# 9__ID_Serial.net
KiCad netlist of a schematic drawn in Altium Designer
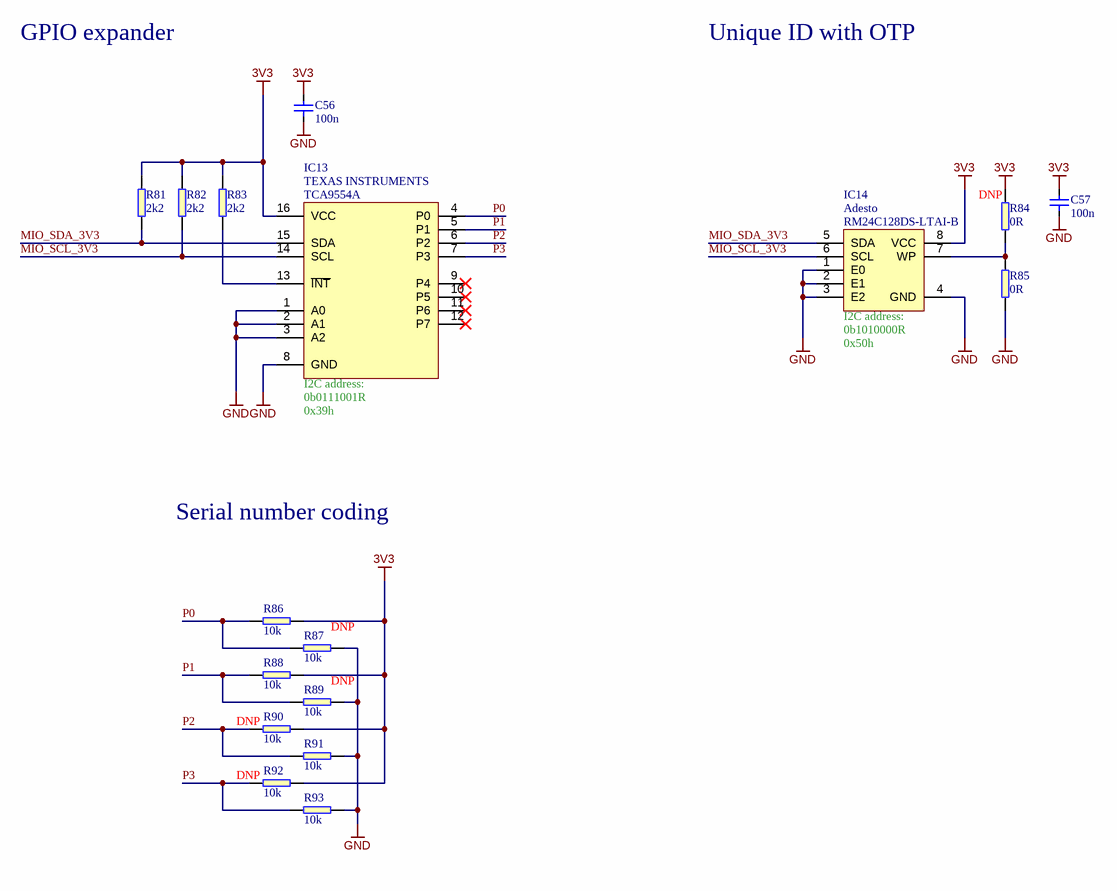
[diagram p0: [9]_ID_Serial.SchDoc]

(export (version "E")
  (design (tool "Eeschema 10.0.6"))
  (components
    (comp (ref "C56")
      (value "100n")
      (footprint "0402")
      (description "MLCC SMT Capacitor 100nF 0402")
      (fields (field (name "PART NUMBER") "C_100n_0402") (field (name "VOLTAGE") "10V"))
      (libsource (lib "Zynq-Video-Board-Rev-1.2") (part "C_100n_0402"))
    )
    (comp (ref "C57")
      (value "100n")
      (footprint "0402")
      (description "MLCC SMT Capacitor 100nF 0402")
      (fields (field (name "PART NUMBER") "C_100n_0402") (field (name "VOLTAGE") "10V"))
      (libsource (lib "Zynq-Video-Board-Rev-1.2") (part "C_100n_0402"))
    )
    (comp (ref "IC13")
      (value "TCA9554A")
      (footprint "DBQ0016A")
      (description "Remote 8bit I2C SMBus I/O expander")
      (fields (field (name "MANUFACTURER") "TEXAS INSTRUMENTS") (field (name "PART SYMBOL") "TCA9554A"))
      (libsource (lib "Zynq-Video-Board-Rev-1.2") (part "TCA9554A"))
    )
    (comp (ref "IC14")
      (value "RM24C128DS-LTAI-B")
      (footprint "TSSOP-8")
      (description "EEPROM with UID and OTP registers.")
      (fields
        (field (name "PART NUMBER") "RM24C128DS")
        (field (name "MANUFACTURER") "Adesto")
        (field (name "PART SYMBOL") "RM24C128DS-LTAI-B")
      )
      (libsource (lib "Zynq-Video-Board-Rev-1.2") (part "RM24C128DS"))
    )
    (comp (ref "R81")
      (value "2k2")
      (footprint "0402")
      (description "SMT Resistor 2k2 0402")
      (fields (field (name "PART NUMBER") "R_2k2_0402") (field (name "TOLERANCE") "5%"))
      (libsource (lib "Zynq-Video-Board-Rev-1.2") (part "R_2k2_0402"))
    )
    (comp (ref "R82")
      (value "2k2")
      (footprint "0402")
      (description "SMT Resistor 2k2 0402")
      (fields (field (name "PART NUMBER") "R_2k2_0402") (field (name "TOLERANCE") "5%"))
      (libsource (lib "Zynq-Video-Board-Rev-1.2") (part "R_2k2_0402"))
    )
    (comp (ref "R83")
      (value "2k2")
      (footprint "0402")
      (description "SMT Resistor 2k2 0402")
      (fields (field (name "PART NUMBER") "R_2k2_0402") (field (name "TOLERANCE") "5%"))
      (libsource (lib "Zynq-Video-Board-Rev-1.2") (part "R_2k2_0402"))
    )
    (comp (ref "R84")
      (value "0R")
      (footprint "0402")
      (description "SMT Resistor 0R 0402")
      (fields (field (name "PART NUMBER") "R_0R_0402") (field (name "MANUFACTURER") "MULTICOMP"))
      (libsource (lib "Zynq-Video-Board-Rev-1.2") (part "R_0R_0402"))
    )
    (comp (ref "R85")
      (value "0R")
      (footprint "0402")
      (description "SMT Resistor 0R 0402")
      (fields (field (name "PART NUMBER") "R_0R_0402") (field (name "MANUFACTURER") "MULTICOMP"))
      (libsource (lib "Zynq-Video-Board-Rev-1.2") (part "R_0R_0402"))
    )
    (comp (ref "R86")
      (value "10k")
      (footprint "0402")
      (description "SMT Resistor 10k 0402")
      (fields (field (name "PART NUMBER") "R_10k_0402") (field (name "TOLERANCE") "1%"))
      (libsource (lib "Zynq-Video-Board-Rev-1.2") (part "R_10k_0402"))
    )
    (comp (ref "R87")
      (value "10k")
      (footprint "0402")
      (description "SMT Resistor 10k 0402")
      (fields (field (name "PART NUMBER") "R_10k_0402") (field (name "TOLERANCE") "1%"))
      (libsource (lib "Zynq-Video-Board-Rev-1.2") (part "R_10k_0402"))
    )
    (comp (ref "R88")
      (value "10k")
      (footprint "0402")
      (description "SMT Resistor 10k 0402")
      (fields (field (name "PART NUMBER") "R_10k_0402") (field (name "TOLERANCE") "1%"))
      (libsource (lib "Zynq-Video-Board-Rev-1.2") (part "R_10k_0402"))
    )
    (comp (ref "R89")
      (value "10k")
      (footprint "0402")
      (description "SMT Resistor 10k 0402")
      (fields (field (name "PART NUMBER") "R_10k_0402") (field (name "TOLERANCE") "1%"))
      (libsource (lib "Zynq-Video-Board-Rev-1.2") (part "R_10k_0402"))
    )
    (comp (ref "R90")
      (value "10k")
      (footprint "0402")
      (description "SMT Resistor 10k 0402")
      (fields (field (name "PART NUMBER") "R_10k_0402") (field (name "TOLERANCE") "1%"))
      (libsource (lib "Zynq-Video-Board-Rev-1.2") (part "R_10k_0402"))
    )
    (comp (ref "R91")
      (value "10k")
      (footprint "0402")
      (description "SMT Resistor 10k 0402")
      (fields (field (name "PART NUMBER") "R_10k_0402") (field (name "TOLERANCE") "1%"))
      (libsource (lib "Zynq-Video-Board-Rev-1.2") (part "R_10k_0402"))
    )
    (comp (ref "R92")
      (value "10k")
      (footprint "0402")
      (description "SMT Resistor 10k 0402")
      (fields (field (name "PART NUMBER") "R_10k_0402") (field (name "TOLERANCE") "1%"))
      (libsource (lib "Zynq-Video-Board-Rev-1.2") (part "R_10k_0402"))
    )
    (comp (ref "R93")
      (value "10k")
      (footprint "0402")
      (description "SMT Resistor 10k 0402")
      (fields (field (name "PART NUMBER") "R_10k_0402") (field (name "TOLERANCE") "1%"))
      (libsource (lib "Zynq-Video-Board-Rev-1.2") (part "R_10k_0402"))
    )
  )
  (nets
    (net (code "1") (name "/MIO_SCL_3V3") (class "Default")
      (node (ref "IC13") (pin "14") (pinfunction "SCL_14") (pintype "passive"))
      (node (ref "IC14") (pin "6") (pinfunction "SCL_6") (pintype "passive"))
      (node (ref "R82") (pin "1") (pintype "passive"))
    )
    (net (code "2") (name "/MIO_SDA_3V3") (class "Default")
      (node (ref "IC13") (pin "15") (pinfunction "SDA_15") (pintype "passive"))
      (node (ref "IC14") (pin "5") (pinfunction "SDA_5") (pintype "passive"))
      (node (ref "R81") (pin "1") (pintype "passive"))
    )
    (net (code "3") (name "/P0") (class "Default")
      (node (ref "IC13") (pin "4") (pinfunction "P0_4") (pintype "passive"))
      (node (ref "R86") (pin "1") (pintype "passive"))
      (node (ref "R87") (pin "1") (pintype "passive"))
    )
    (net (code "4") (name "/P1") (class "Default")
      (node (ref "IC13") (pin "5") (pinfunction "P1_5") (pintype "passive"))
      (node (ref "R88") (pin "1") (pintype "passive"))
      (node (ref "R89") (pin "1") (pintype "passive"))
    )
    (net (code "5") (name "/P2") (class "Default")
      (node (ref "IC13") (pin "6") (pinfunction "P2_6") (pintype "passive"))
      (node (ref "R90") (pin "1") (pintype "passive"))
      (node (ref "R91") (pin "1") (pintype "passive"))
    )
    (net (code "6") (name "/P3") (class "Default")
      (node (ref "IC13") (pin "7") (pinfunction "P3_7") (pintype "passive"))
      (node (ref "R92") (pin "1") (pintype "passive"))
      (node (ref "R93") (pin "1") (pintype "passive"))
    )
    (net (code "7") (name "3V3") (class "Default")
      (node (ref "C56") (pin "2") (pinfunction "2_2") (pintype "passive"))
      (node (ref "C57") (pin "2") (pinfunction "2_2") (pintype "passive"))
      (node (ref "IC13") (pin "16") (pinfunction "VCC_16") (pintype "passive"))
      (node (ref "IC14") (pin "8") (pinfunction "VCC_8") (pintype "passive"))
      (node (ref "R81") (pin "2") (pintype "passive"))
      (node (ref "R82") (pin "2") (pintype "passive"))
      (node (ref "R83") (pin "2") (pintype "passive"))
      (node (ref "R84") (pin "2") (pintype "passive"))
      (node (ref "R86") (pin "2") (pintype "passive"))
      (node (ref "R88") (pin "2") (pintype "passive"))
      (node (ref "R90") (pin "2") (pintype "passive"))
      (node (ref "R92") (pin "2") (pintype "passive"))
    )
    (net (code "8") (name "GND") (class "Default")
      (node (ref "C56") (pin "1") (pinfunction "1_1") (pintype "passive"))
      (node (ref "C57") (pin "1") (pinfunction "1_1") (pintype "passive"))
      (node (ref "IC13") (pin "1") (pinfunction "A0_1") (pintype "passive"))
      (node (ref "IC13") (pin "2") (pinfunction "A1_2") (pintype "passive"))
      (node (ref "IC13") (pin "3") (pinfunction "A2_3") (pintype "passive"))
      (node (ref "IC13") (pin "8") (pinfunction "GND_8") (pintype "passive"))
      (node (ref "IC14") (pin "1") (pinfunction "E0_1") (pintype "passive"))
      (node (ref "IC14") (pin "2") (pinfunction "E1_2") (pintype "passive"))
      (node (ref "IC14") (pin "3") (pinfunction "E2_3") (pintype "passive"))
      (node (ref "IC14") (pin "4") (pinfunction "GND_4") (pintype "passive"))
      (node (ref "R85") (pin "1") (pintype "passive"))
      (node (ref "R87") (pin "2") (pintype "passive"))
      (node (ref "R89") (pin "2") (pintype "passive"))
      (node (ref "R91") (pin "2") (pintype "passive"))
      (node (ref "R93") (pin "2") (pintype "passive"))
    )
    (net (code "9") (name "Net-(IC13-~{INT})") (class "Default")
      (node (ref "IC13") (pin "13") (pinfunction "~{INT}_13") (pintype "passive"))
      (node (ref "R83") (pin "1") (pintype "passive"))
    )
    (net (code "10") (name "Net-(IC14-WP)") (class "Default")
      (node (ref "IC14") (pin "7") (pinfunction "WP_7") (pintype "passive"))
      (node (ref "R84") (pin "1") (pintype "passive"))
      (node (ref "R85") (pin "2") (pintype "passive"))
    )
    (net (code "11") (name "unconnected-(IC13-P4-Pad9)") (class "Default")
      (node (ref "IC13") (pin "9") (pinfunction "P4_9") (pintype "passive+no_connect"))
    )
    (net (code "12") (name "unconnected-(IC13-P5-Pad10)") (class "Default")
      (node (ref "IC13") (pin "10") (pinfunction "P5_10") (pintype "passive+no_connect"))
    )
    (net (code "13") (name "unconnected-(IC13-P6-Pad11)") (class "Default")
      (node (ref "IC13") (pin "11") (pinfunction "P6_11") (pintype "passive+no_connect"))
    )
    (net (code "14") (name "unconnected-(IC13-P7-Pad12)") (class "Default")
      (node (ref "IC13") (pin "12") (pinfunction "P7_12") (pintype "passive+no_connect"))
    )
  )
)
